# Maix-II.net
KiCad netlist of a schematic drawn in Altium Designer
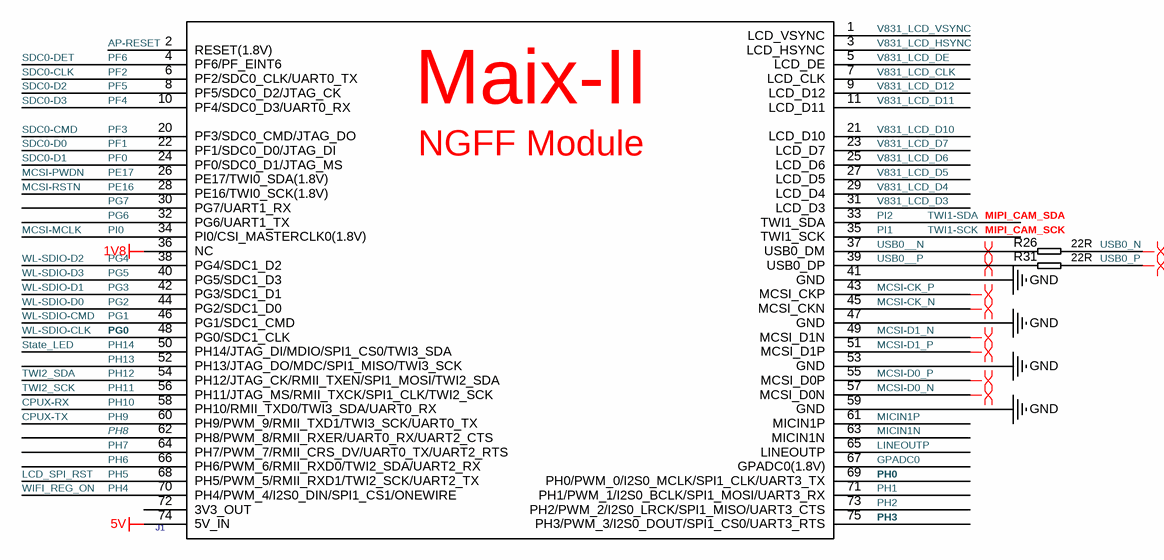
[diagram p0: Maix-II.SchDoc]

(export (version "E")
  (design (tool "Eeschema 10.0.6"))
  (components
    (comp (ref "J1")
      (value "NGFF-67P_B-KEY座子 4.2H高")
      (footprint "M2-67P0R50_B_FEMALE")
      (libsource (lib "V831_Dock_3060") (part "NGFF-67P_B-MALE"))
    )
    (comp (ref "R26") (value "22R") (footprint "R0402_M") (libsource (lib "MaixDuino_4.30-Sch") (part "R")))
    (comp (ref "R31") (value "22R") (footprint "R0402_M") (libsource (lib "MaixDuino_4.30-Sch") (part "R")))
  )
  (nets
    (net (code "1") (name "/AP-RESET") (class "Default")
      (node (ref "J1") (pin "2") (pinfunction "RESET(1.8V)_2") (pintype "passive"))
    )
    (net (code "2") (name "/CPUX-RX") (class "Default")
      (node (ref "J1") (pin "58") (pinfunction "PH10/RMII_TXD0/TWI3_SDA/UART0_RX_58") (pintype "passive"))
    )
    (net (code "3") (name "/CPUX-TX") (class "Default")
      (node (ref "J1") (pin "60") (pinfunction "PH9/PWM_9/RMII_TXD1/TWI3_SCK/UART0_TX_60") (pintype "passive"))
    )
    (net (code "4") (name "/GPADC0") (class "Default")
      (node (ref "J1") (pin "67") (pinfunction "GPADC0(1.8V)_67") (pintype "passive"))
    )
    (net (code "5") (name "/LCD_SPI_RST") (class "Default")
      (node (ref "J1") (pin "68") (pinfunction "PH5/PWM_5/RMII_RXD1/TWI2_SCK/UART2_TX_68") (pintype "passive"))
    )
    (net (code "6") (name "/LINEOUTP") (class "Default")
      (node (ref "J1") (pin "65") (pinfunction "LINEOUTP_65") (pintype "passive"))
    )
    (net (code "7") (name "/MCSI-CK_N") (class "Default")
      (node (ref "J1") (pin "45") (pinfunction "MCSI_CKN_45") (pintype "passive"))
    )
    (net (code "8") (name "/MCSI-CK_P") (class "Default")
      (node (ref "J1") (pin "43") (pinfunction "MCSI_CKP_43") (pintype "passive"))
    )
    (net (code "9") (name "/MCSI-D0_N") (class "Default")
      (node (ref "J1") (pin "57") (pinfunction "MCSI_D0N_57") (pintype "passive"))
    )
    (net (code "10") (name "/MCSI-D0_P") (class "Default")
      (node (ref "J1") (pin "55") (pinfunction "MCSI_D0P_55") (pintype "passive"))
    )
    (net (code "11") (name "/MCSI-D1_N") (class "Default")
      (node (ref "J1") (pin "49") (pinfunction "MCSI_D1N_49") (pintype "passive"))
    )
    (net (code "12") (name "/MCSI-D1_P") (class "Default")
      (node (ref "J1") (pin "51") (pinfunction "MCSI_D1P_51") (pintype "passive"))
    )
    (net (code "13") (name "/MCSI-MCLK") (class "Default")
      (node (ref "J1") (pin "34") (pinfunction "PI0/CSI_MASTERCLK0(1.8V)_34") (pintype "passive"))
    )
    (net (code "14") (name "/MCSI-PWDN") (class "Default")
      (node (ref "J1") (pin "26") (pinfunction "PE17/TWI0_SDA(1.8V)_26") (pintype "passive"))
    )
    (net (code "15") (name "/MCSI-RSTN") (class "Default")
      (node (ref "J1") (pin "28") (pinfunction "PE16/TWI0_SCK(1.8V)_28") (pintype "passive"))
    )
    (net (code "16") (name "/MICIN1N") (class "Default")
      (node (ref "J1") (pin "63") (pinfunction "MICIN1N_63") (pintype "passive"))
    )
    (net (code "17") (name "/MICIN1P") (class "Default")
      (node (ref "J1") (pin "61") (pinfunction "MICIN1P_61") (pintype "passive"))
    )
    (net (code "18") (name "/PF0") (class "Default")
      (node (ref "J1") (pin "24") (pinfunction "PF0/SDC0_D1/JTAG_MS_24") (pintype "passive"))
    )
    (net (code "19") (name "/PF1") (class "Default")
      (node (ref "J1") (pin "22") (pinfunction "PF1/SDC0_D0/JTAG_DI_22") (pintype "passive"))
    )
    (net (code "20") (name "/PF2") (class "Default")
      (node (ref "J1") (pin "6") (pinfunction "PF2/SDC0_CLK/UART0_TX_6") (pintype "passive"))
    )
    (net (code "21") (name "/PF3") (class "Default")
      (node (ref "J1") (pin "20") (pinfunction "PF3/SDC0_CMD/JTAG_DO_20") (pintype "passive"))
    )
    (net (code "22") (name "/PF4") (class "Default")
      (node (ref "J1") (pin "10") (pinfunction "PF4/SDC0_D3/UART0_RX_10") (pintype "passive"))
    )
    (net (code "23") (name "/PF5") (class "Default")
      (node (ref "J1") (pin "8") (pinfunction "PF5/SDC0_D2/JTAG_CK_8") (pintype "passive"))
    )
    (net (code "24") (name "/PF6") (class "Default")
      (node (ref "J1") (pin "4") (pinfunction "PF6/PF_EINT6_4") (pintype "passive"))
    )
    (net (code "25") (name "/PG0") (class "Default")
      (node (ref "J1") (pin "48") (pinfunction "PG0/SDC1_CLK_48") (pintype "passive"))
    )
    (net (code "26") (name "/PG1") (class "Default")
      (node (ref "J1") (pin "46") (pinfunction "PG1/SDC1_CMD_46") (pintype "passive"))
    )
    (net (code "27") (name "/PG2") (class "Default")
      (node (ref "J1") (pin "44") (pinfunction "PG2/SDC1_D0_44") (pintype "passive"))
    )
    (net (code "28") (name "/PG3") (class "Default")
      (node (ref "J1") (pin "42") (pinfunction "PG3/SDC1_D1_42") (pintype "passive"))
    )
    (net (code "29") (name "/PG4") (class "Default")
      (node (ref "J1") (pin "38") (pinfunction "PG4/SDC1_D2_38") (pintype "passive"))
    )
    (net (code "30") (name "/PG5") (class "Default")
      (node (ref "J1") (pin "40") (pinfunction "PG5/SDC1_D3_40") (pintype "passive"))
    )
    (net (code "31") (name "/PG6") (class "Default")
      (node (ref "J1") (pin "32") (pinfunction "PG6/UART1_TX_32") (pintype "passive"))
    )
    (net (code "32") (name "/PG7") (class "Default")
      (node (ref "J1") (pin "30") (pinfunction "PG7/UART1_RX_30") (pintype "passive"))
    )
    (net (code "33") (name "/PH0") (class "Default")
      (node (ref "J1") (pin "69") (pinfunction "PH0/PWM_0/I2S0_MCLK/SPI1_CLK/UART3_TX_69") (pintype "passive"))
    )
    (net (code "34") (name "/PH1") (class "Default")
      (node (ref "J1") (pin "71") (pinfunction "PH1/PWM_1/I2S0_BCLK/SPI1_MOSI/UART3_RX_71") (pintype "passive"))
    )
    (net (code "35") (name "/PH2") (class "Default")
      (node (ref "J1") (pin "73") (pinfunction "PH2/PWM_2/I2S0_LRCK/SPI1_MISO/UART3_CTS_73") (pintype "passive"))
    )
    (net (code "36") (name "/PH3") (class "Default")
      (node (ref "J1") (pin "75") (pinfunction "PH3/PWM_3/I2S0_DOUT/SPI1_CS0/UART3_RTS_75") (pintype "passive"))
    )
    (net (code "37") (name "/PH4") (class "Default")
      (node (ref "J1") (pin "70") (pinfunction "PH4/PWM_4/I2S0_DIN/SPI1_CS1/ONEWIRE_70") (pintype "passive"))
    )
    (net (code "38") (name "/PH6") (class "Default")
      (node (ref "J1") (pin "66") (pinfunction "PH6/PWM_6/RMII_RXD0/TWI2_SDA/UART2_RX_66") (pintype "passive"))
    )
    (net (code "39") (name "/PH7") (class "Default")
      (node (ref "J1") (pin "64") (pinfunction "PH7/PWM_7/RMII_CRS_DV/UART0_TX/UART2_RTS_64") (pintype "passive"))
    )
    (net (code "40") (name "/PH8") (class "Default")
      (node (ref "J1") (pin "62") (pinfunction "PH8/PWM_8/RMII_RXER/UART0_RX/UART2_CTS_62") (pintype "passive"))
    )
    (net (code "41") (name "/PH11") (class "Default")
      (node (ref "J1") (pin "56") (pinfunction "PH11/JTAG_MS/RMII_TXCK/SPI1_CLK/TWI2_SCK_56") (pintype "passive"))
    )
    (net (code "42") (name "/PH12") (class "Default")
      (node (ref "J1") (pin "54") (pinfunction "PH12/JTAG_CK/RMII_TXEN/SPI1_MOSI/TWI2_SDA_54") (pintype "passive"))
    )
    (net (code "43") (name "/PH13") (class "Default")
      (node (ref "J1") (pin "52") (pinfunction "PH13/JTAG_DO/MDC/SPI1_MISO/TWI3_SCK_52") (pintype "passive"))
    )
    (net (code "44") (name "/PH14") (class "Default")
      (node (ref "J1") (pin "50") (pinfunction "PH14/JTAG_DI/MDIO/SPI1_CS0/TWI3_SDA_50") (pintype "passive"))
    )
    (net (code "45") (name "/PI1") (class "Default")
      (node (ref "J1") (pin "35") (pinfunction "TWI1_SCK_35") (pintype "passive"))
    )
    (net (code "46") (name "/PI2") (class "Default")
      (node (ref "J1") (pin "33") (pinfunction "TWI1_SDA_33") (pintype "passive"))
    )
    (net (code "47") (name "/USB0_N") (class "Default")
      (node (ref "R26") (pin "1") (pinfunction "1_1") (pintype "passive"))
    )
    (net (code "48") (name "/USB0_P") (class "Default")
      (node (ref "R31") (pin "1") (pinfunction "1_1") (pintype "passive"))
    )
    (net (code "49") (name "/USB0__N") (class "Default")
      (node (ref "J1") (pin "37") (pinfunction "USB0_DM_37") (pintype "passive"))
      (node (ref "R26") (pin "2") (pinfunction "2_2") (pintype "passive"))
    )
    (net (code "50") (name "/USB0__P") (class "Default")
      (node (ref "J1") (pin "39") (pinfunction "USB0_DP_39") (pintype "passive"))
      (node (ref "R31") (pin "2") (pinfunction "2_2") (pintype "passive"))
    )
    (net (code "51") (name "/V831_LCD_CLK") (class "Default")
      (node (ref "J1") (pin "7") (pinfunction "LCD_CLK_7") (pintype "passive"))
    )
    (net (code "52") (name "/V831_LCD_D3") (class "Default")
      (node (ref "J1") (pin "31") (pinfunction "LCD_D3_31") (pintype "passive"))
    )
    (net (code "53") (name "/V831_LCD_D4") (class "Default")
      (node (ref "J1") (pin "29") (pinfunction "LCD_D4_29") (pintype "passive"))
    )
    (net (code "54") (name "/V831_LCD_D5") (class "Default")
      (node (ref "J1") (pin "27") (pinfunction "LCD_D5_27") (pintype "passive"))
    )
    (net (code "55") (name "/V831_LCD_D6") (class "Default")
      (node (ref "J1") (pin "25") (pinfunction "LCD_D6_25") (pintype "passive"))
    )
    (net (code "56") (name "/V831_LCD_D7") (class "Default")
      (node (ref "J1") (pin "23") (pinfunction "LCD_D7_23") (pintype "passive"))
    )
    (net (code "57") (name "/V831_LCD_D10") (class "Default")
      (node (ref "J1") (pin "21") (pinfunction "LCD_D10_21") (pintype "passive"))
    )
    (net (code "58") (name "/V831_LCD_D11") (class "Default")
      (node (ref "J1") (pin "11") (pinfunction "LCD_D11_11") (pintype "passive"))
    )
    (net (code "59") (name "/V831_LCD_D12") (class "Default")
      (node (ref "J1") (pin "9") (pinfunction "LCD_D12_9") (pintype "passive"))
    )
    (net (code "60") (name "/V831_LCD_DE") (class "Default")
      (node (ref "J1") (pin "5") (pinfunction "LCD_DE_5") (pintype "passive"))
    )
    (net (code "61") (name "/V831_LCD_HSYNC") (class "Default")
      (node (ref "J1") (pin "3") (pinfunction "LCD_HSYNC_3") (pintype "passive"))
    )
    (net (code "62") (name "/V831_LCD_VSYNC") (class "Default")
      (node (ref "J1") (pin "1") (pinfunction "LCD_VSYNC_1") (pintype "passive"))
    )
    (net (code "63") (name "1V8") (class "Default")
      (node (ref "J1") (pin "36") (pinfunction "NC_36") (pintype "passive"))
    )
    (net (code "64") (name "5V") (class "Default")
      (node (ref "J1") (pin "74") (pinfunction "5V_IN_74") (pintype "passive"))
    )
    (net (code "65") (name "GND") (class "Default")
      (node (ref "J1") (pin "41") (pinfunction "GND_41") (pintype "passive"))
      (node (ref "J1") (pin "47") (pinfunction "GND_47") (pintype "passive"))
      (node (ref "J1") (pin "53") (pinfunction "GND_53") (pintype "passive"))
      (node (ref "J1") (pin "59") (pinfunction "GND_59") (pintype "passive"))
    )
    (net (code "66") (name "unconnected-(J1-3V3_OUT-Pad72)") (class "Default")
      (node (ref "J1") (pin "72") (pinfunction "3V3_OUT_72") (pintype "passive"))
    )
  )
)
